# Power_supply.net
KiCad netlist of a schematic drawn in Altium Designer
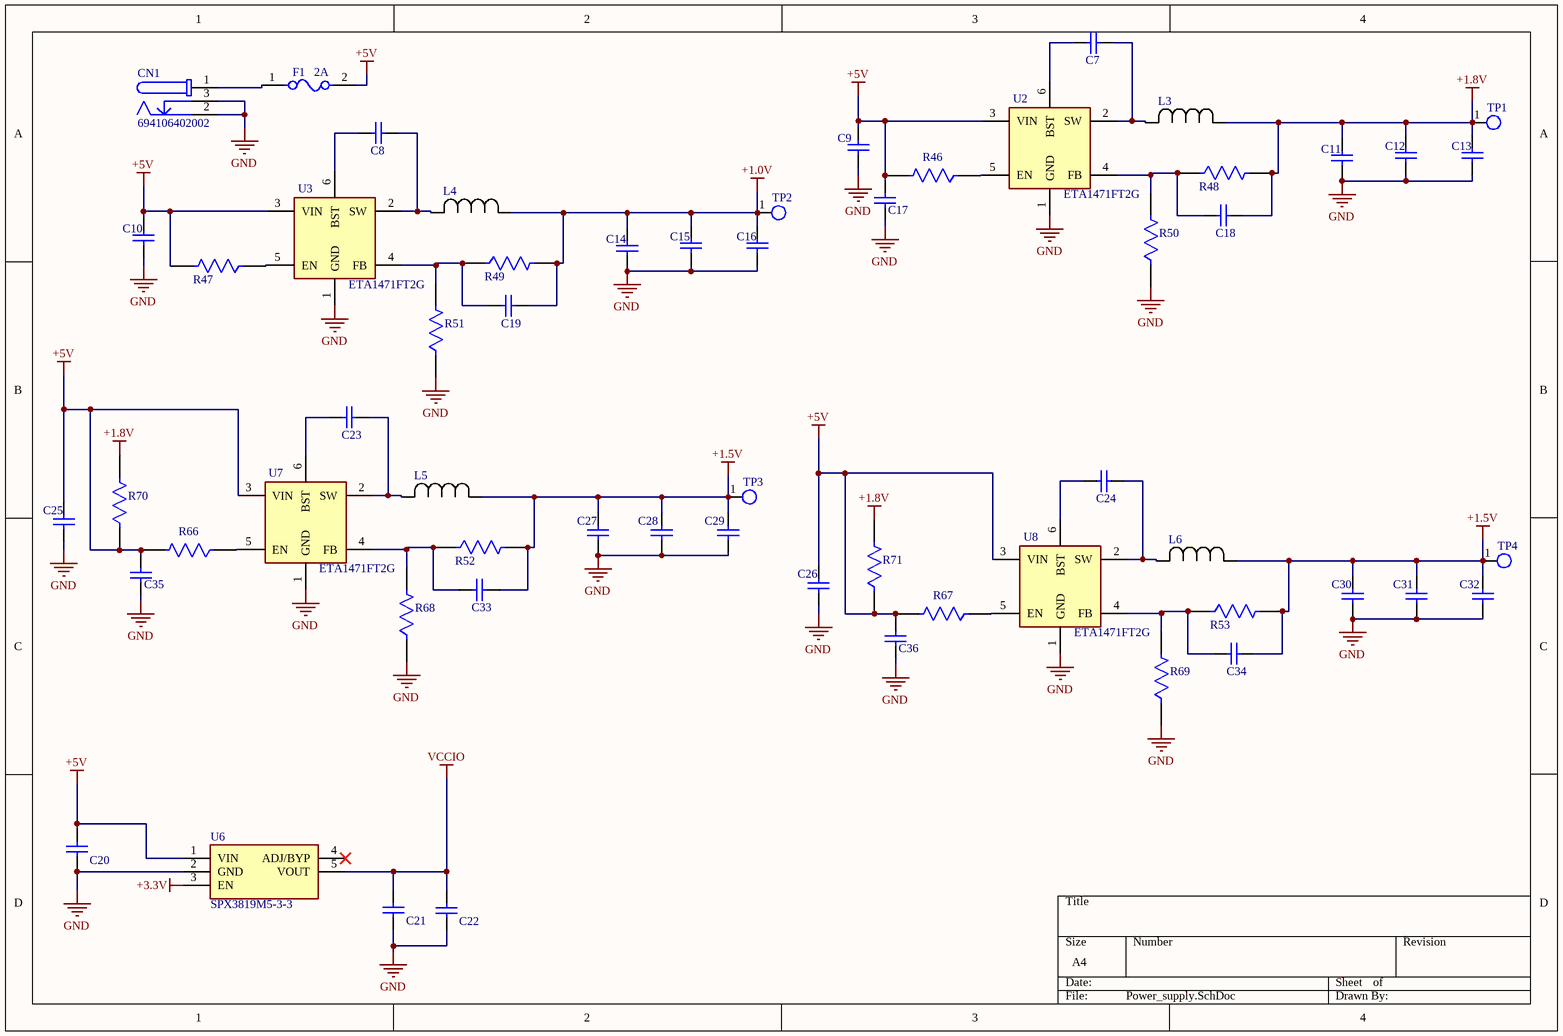
[diagram p0: Power_supply.SchDoc]

(export (version "E")
  (design (tool "Eeschema 10.0.6"))
  (components
    (comp (ref "C7")
      (value "VJ0805Y152KXAAC")
      (footprint "CAPC2013X145X48NL20T23")
      (fields (field (name "MANUFACTURER") "Vitramon"))
      (libsource (lib "Altium Content Vault") (part "CAP"))
    )
    (comp (ref "C8")
      (value "VJ0805Y152KXAAC")
      (footprint "CAPC2013X145X48NL20T23")
      (fields (field (name "MANUFACTURER") "Vitramon"))
      (libsource (lib "Altium Content Vault") (part "CAP"))
    )
    (comp (ref "C9")
      (value "VJ0805Y152KXAAC")
      (footprint "CAPC2013X145X48NL20T23")
      (fields (field (name "MANUFACTURER") "Vitramon"))
      (libsource (lib "Altium Content Vault") (part "CAP"))
    )
    (comp (ref "C10")
      (value "VJ0805Y152KXAAC")
      (footprint "CAPC2013X145X48NL20T23")
      (fields (field (name "MANUFACTURER") "Vitramon"))
      (libsource (lib "Altium Content Vault") (part "CAP"))
    )
    (comp (ref "C11")
      (value "VJ0805Y152KXAAC")
      (footprint "CAPC2013X145X48NL20T23")
      (fields (field (name "MANUFACTURER") "Vitramon"))
      (libsource (lib "Altium Content Vault") (part "CAP"))
    )
    (comp (ref "C12")
      (value "VJ0805Y152KXAAC")
      (footprint "CAPC2013X145X48NL20T23")
      (fields (field (name "MANUFACTURER") "Vitramon"))
      (libsource (lib "Altium Content Vault") (part "CAP"))
    )
    (comp (ref "C13")
      (value "VJ0805Y152KXAAC")
      (footprint "CAPC2013X145X48NL20T23")
      (fields (field (name "MANUFACTURER") "Vitramon"))
      (libsource (lib "Altium Content Vault") (part "CAP"))
    )
    (comp (ref "C14")
      (value "VJ0805Y152KXAAC")
      (footprint "CAPC2013X145X48NL20T23")
      (fields (field (name "MANUFACTURER") "Vitramon"))
      (libsource (lib "Altium Content Vault") (part "CAP"))
    )
    (comp (ref "C15")
      (value "VJ0805Y152KXAAC")
      (footprint "CAPC2013X145X48NL20T23")
      (fields (field (name "MANUFACTURER") "Vitramon"))
      (libsource (lib "Altium Content Vault") (part "CAP"))
    )
    (comp (ref "C16")
      (value "VJ0805Y152KXAAC")
      (footprint "CAPC2013X145X48NL20T23")
      (fields (field (name "MANUFACTURER") "Vitramon"))
      (libsource (lib "Altium Content Vault") (part "CAP"))
    )
    (comp (ref "C17")
      (value "VJ0805Y152KXAAC")
      (footprint "CAPC2013X145X48NL20T23")
      (fields (field (name "MANUFACTURER") "Vitramon"))
      (libsource (lib "Altium Content Vault") (part "CAP"))
    )
    (comp (ref "C18")
      (value "VJ0805Y152KXAAC")
      (footprint "CAPC2013X145X48NL20T23")
      (fields (field (name "MANUFACTURER") "Vitramon"))
      (libsource (lib "Altium Content Vault") (part "CAP"))
    )
    (comp (ref "C19")
      (value "VJ0805Y152KXAAC")
      (footprint "CAPC2013X145X48NL20T23")
      (fields (field (name "MANUFACTURER") "Vitramon"))
      (libsource (lib "Altium Content Vault") (part "CAP"))
    )
    (comp (ref "C20")
      (value "VJ0805Y152KXAAC")
      (footprint "CAPC2013X145X48NL20T23")
      (fields (field (name "MANUFACTURER") "Vitramon"))
      (libsource (lib "Altium Content Vault") (part "CAP"))
    )
    (comp (ref "C21")
      (value "VJ0805Y152KXAAC")
      (footprint "CAPC2013X145X48NL20T23")
      (fields (field (name "MANUFACTURER") "Vitramon"))
      (libsource (lib "Altium Content Vault") (part "CAP"))
    )
    (comp (ref "C22")
      (value "VJ0805Y152KXAAC")
      (footprint "CAPC2013X145X48NL20T23")
      (fields (field (name "MANUFACTURER") "Vitramon"))
      (libsource (lib "Altium Content Vault") (part "CAP"))
    )
    (comp (ref "C23")
      (value "VJ0805Y152KXAAC")
      (footprint "CAPC2013X145X48NL20T23")
      (fields (field (name "MANUFACTURER") "Vitramon"))
      (libsource (lib "Altium Content Vault") (part "CAP"))
    )
    (comp (ref "C24")
      (value "VJ0805Y152KXAAC")
      (footprint "CAPC2013X145X48NL20T23")
      (fields (field (name "MANUFACTURER") "Vitramon"))
      (libsource (lib "Altium Content Vault") (part "CAP"))
    )
    (comp (ref "C25")
      (value "VJ0805Y152KXAAC")
      (footprint "CAPC2013X145X48NL20T23")
      (fields (field (name "MANUFACTURER") "Vitramon"))
      (libsource (lib "Altium Content Vault") (part "CAP"))
    )
    (comp (ref "C26")
      (value "VJ0805Y152KXAAC")
      (footprint "CAPC2013X145X48NL20T23")
      (fields (field (name "MANUFACTURER") "Vitramon"))
      (libsource (lib "Altium Content Vault") (part "CAP"))
    )
    (comp (ref "C27")
      (value "VJ0805Y152KXAAC")
      (footprint "CAPC2013X145X48NL20T23")
      (fields (field (name "MANUFACTURER") "Vitramon"))
      (libsource (lib "Altium Content Vault") (part "CAP"))
    )
    (comp (ref "C28")
      (value "VJ0805Y152KXAAC")
      (footprint "CAPC2013X145X48NL20T23")
      (fields (field (name "MANUFACTURER") "Vitramon"))
      (libsource (lib "Altium Content Vault") (part "CAP"))
    )
    (comp (ref "C29")
      (value "VJ0805Y152KXAAC")
      (footprint "CAPC2013X145X48NL20T23")
      (fields (field (name "MANUFACTURER") "Vitramon"))
      (libsource (lib "Altium Content Vault") (part "CAP"))
    )
    (comp (ref "C30")
      (value "VJ0805Y152KXAAC")
      (footprint "CAPC2013X145X48NL20T23")
      (fields (field (name "MANUFACTURER") "Vitramon"))
      (libsource (lib "Altium Content Vault") (part "CAP"))
    )
    (comp (ref "C31")
      (value "VJ0805Y152KXAAC")
      (footprint "CAPC2013X145X48NL20T23")
      (fields (field (name "MANUFACTURER") "Vitramon"))
      (libsource (lib "Altium Content Vault") (part "CAP"))
    )
    (comp (ref "C32")
      (value "VJ0805Y152KXAAC")
      (footprint "CAPC2013X145X48NL20T23")
      (fields (field (name "MANUFACTURER") "Vitramon"))
      (libsource (lib "Altium Content Vault") (part "CAP"))
    )
    (comp (ref "C33")
      (value "VJ0805Y152KXAAC")
      (footprint "CAPC2013X145X48NL20T23")
      (fields (field (name "MANUFACTURER") "Vitramon"))
      (libsource (lib "Altium Content Vault") (part "CAP"))
    )
    (comp (ref "C34")
      (value "VJ0805Y152KXAAC")
      (footprint "CAPC2013X145X48NL20T23")
      (fields (field (name "MANUFACTURER") "Vitramon"))
      (libsource (lib "Altium Content Vault") (part "CAP"))
    )
    (comp (ref "C35")
      (value "VJ0805Y152KXAAC")
      (footprint "CAPC2013X145X48NL20T23")
      (fields (field (name "MANUFACTURER") "Vitramon"))
      (libsource (lib "Altium Content Vault") (part "CAP"))
    )
    (comp (ref "C36")
      (value "VJ0805Y152KXAAC")
      (footprint "CAPC2013X145X48NL20T23")
      (fields (field (name "MANUFACTURER") "Vitramon"))
      (libsource (lib "Altium Content Vault") (part "CAP"))
    )
    (comp (ref "CN1")
      (value "694106402002")
      (footprint "694106402002")
      (description "DC Power Jack Connector WR-DC, Male, Vertical, THT, 3 A, 20 V")
      (libsource (lib "Altium Content Vault") (part "DC Power Jack"))
    )
    (comp (ref "F1")
      (value "2A")
      (footprint "FP-0683G-MFG")
      (description "FUSE SLOW 125VDC 350VAC 2A")
      (libsource (lib "Altium Content Vault") (part "5bcf9b9f640e542cf0359d10258e979"))
    )
    (comp (ref "L3")
      (value "ASPIAIG-FLR4020-3R3M-T")
      (footprint "IND_ASPIAIG-F4020_ABR")
      (description "Description")
      (fields (field (name "COPYRIGHT") "Copyright (C) 2026 Ultra Librarian. All rights reserved."))
      (libsource (lib "ASPIAIG-FLR4020-3R3M-T") (part "ASPIAIG-FLR4020-3R3M-T"))
    )
    (comp (ref "L4")
      (value "ASPIAIG-FLR4020-3R3M-T")
      (footprint "IND_ASPIAIG-F4020_ABR")
      (description "Description")
      (fields (field (name "COPYRIGHT") "Copyright (C) 2026 Ultra Librarian. All rights reserved."))
      (libsource (lib "ASPIAIG-FLR4020-3R3M-T") (part "ASPIAIG-FLR4020-3R3M-T"))
    )
    (comp (ref "L5")
      (value "ASPIAIG-FLR4020-3R3M-T")
      (footprint "IND_ASPIAIG-F4020_ABR")
      (description "Description")
      (fields (field (name "COPYRIGHT") "Copyright (C) 2026 Ultra Librarian. All rights reserved."))
      (libsource (lib "ASPIAIG-FLR4020-3R3M-T") (part "ASPIAIG-FLR4020-3R3M-T"))
    )
    (comp (ref "L6")
      (value "ASPIAIG-FLR4020-3R3M-T")
      (footprint "IND_ASPIAIG-F4020_ABR")
      (description "Description")
      (fields (field (name "COPYRIGHT") "Copyright (C) 2026 Ultra Librarian. All rights reserved."))
      (libsource (lib "ASPIAIG-FLR4020-3R3M-T") (part "ASPIAIG-FLR4020-3R3M-T"))
    )
    (comp (ref "R46")
      (value "MCU0805MD4991BP100")
      (footprint "FP-MCU0805-MFG")
      (description "RES 1.05K OHM 0.5% 1/5W 0805")
      (fields (field (name "TOLERANCE") "0.1%"))
      (libsource (lib "Altium Content Vault") (part "1029c3af85768c4190bb7ad29bc67b5"))
    )
    (comp (ref "R47")
      (value "MCU0805MD4991BP100")
      (footprint "FP-MCU0805-MFG")
      (description "RES 1.05K OHM 0.5% 1/5W 0805")
      (fields (field (name "TOLERANCE") "0.1%"))
      (libsource (lib "Altium Content Vault") (part "1029c3af85768c4190bb7ad29bc67b5"))
    )
    (comp (ref "R48")
      (value "MCU0805MD4991BP100")
      (footprint "FP-MCU0805-MFG")
      (description "RES 1.05K OHM 0.5% 1/5W 0805")
      (fields (field (name "TOLERANCE") "0.1%"))
      (libsource (lib "Altium Content Vault") (part "1029c3af85768c4190bb7ad29bc67b5"))
    )
    (comp (ref "R49")
      (value "MCU0805MD4991BP100")
      (footprint "FP-MCU0805-MFG")
      (description "RES 1.05K OHM 0.5% 1/5W 0805")
      (fields (field (name "TOLERANCE") "0.1%"))
      (libsource (lib "Altium Content Vault") (part "1029c3af85768c4190bb7ad29bc67b5"))
    )
    (comp (ref "R50")
      (value "MCU0805MD4991BP100")
      (footprint "FP-MCU0805-MFG")
      (description "RES 1.05K OHM 0.5% 1/5W 0805")
      (fields (field (name "TOLERANCE") "0.1%"))
      (libsource (lib "Altium Content Vault") (part "1029c3af85768c4190bb7ad29bc67b5"))
    )
    (comp (ref "R51")
      (value "MCU0805MD4991BP100")
      (footprint "FP-MCU0805-MFG")
      (description "RES 1.05K OHM 0.5% 1/5W 0805")
      (fields (field (name "TOLERANCE") "0.1%"))
      (libsource (lib "Altium Content Vault") (part "1029c3af85768c4190bb7ad29bc67b5"))
    )
    (comp (ref "R52")
      (value "MCU0805MD4991BP100")
      (footprint "FP-MCU0805-MFG")
      (description "RES 1.05K OHM 0.5% 1/5W 0805")
      (fields (field (name "TOLERANCE") "0.1%"))
      (libsource (lib "Altium Content Vault") (part "1029c3af85768c4190bb7ad29bc67b5"))
    )
    (comp (ref "R53")
      (value "MCU0805MD4991BP100")
      (footprint "FP-MCU0805-MFG")
      (description "RES 1.05K OHM 0.5% 1/5W 0805")
      (fields (field (name "TOLERANCE") "0.1%"))
      (libsource (lib "Altium Content Vault") (part "1029c3af85768c4190bb7ad29bc67b5"))
    )
    (comp (ref "R66")
      (value "MCU0805MD4991BP100")
      (footprint "FP-MCU0805-MFG")
      (description "RES 1.05K OHM 0.5% 1/5W 0805")
      (fields (field (name "TOLERANCE") "0.1%"))
      (libsource (lib "Altium Content Vault") (part "1029c3af85768c4190bb7ad29bc67b5"))
    )
    (comp (ref "R67")
      (value "MCU0805MD4991BP100")
      (footprint "FP-MCU0805-MFG")
      (description "RES 1.05K OHM 0.5% 1/5W 0805")
      (fields (field (name "TOLERANCE") "0.1%"))
      (libsource (lib "Altium Content Vault") (part "1029c3af85768c4190bb7ad29bc67b5"))
    )
    (comp (ref "R68")
      (value "MCU0805MD4991BP100")
      (footprint "FP-MCU0805-MFG")
      (description "RES 1.05K OHM 0.5% 1/5W 0805")
      (fields (field (name "TOLERANCE") "0.1%"))
      (libsource (lib "Altium Content Vault") (part "1029c3af85768c4190bb7ad29bc67b5"))
    )
    (comp (ref "R69")
      (value "MCU0805MD4991BP100")
      (footprint "FP-MCU0805-MFG")
      (description "RES 1.05K OHM 0.5% 1/5W 0805")
      (fields (field (name "TOLERANCE") "0.1%"))
      (libsource (lib "Altium Content Vault") (part "1029c3af85768c4190bb7ad29bc67b5"))
    )
    (comp (ref "R70")
      (value "MCU0805MD4991BP100")
      (footprint "FP-MCU0805-MFG")
      (description "RES 1.05K OHM 0.5% 1/5W 0805")
      (fields (field (name "TOLERANCE") "0.1%"))
      (libsource (lib "Altium Content Vault") (part "1029c3af85768c4190bb7ad29bc67b5"))
    )
    (comp (ref "R71")
      (value "MCU0805MD4991BP100")
      (footprint "FP-MCU0805-MFG")
      (description "RES 1.05K OHM 0.5% 1/5W 0805")
      (fields (field (name "TOLERANCE") "0.1%"))
      (libsource (lib "Altium Content Vault") (part "1029c3af85768c4190bb7ad29bc67b5"))
    )
    (comp (ref "TP1") (value "testpoint") (libsource (lib "licenta") (part "testpoint")))
    (comp (ref "TP2") (value "testpoint") (libsource (lib "licenta") (part "testpoint")))
    (comp (ref "TP3") (value "testpoint") (libsource (lib "licenta") (part "testpoint")))
    (comp (ref "TP4") (value "testpoint") (libsource (lib "licenta") (part "testpoint")))
    (comp (ref "U2")
      (value "ETA1471FT2G")
      (footprint "SamacSys:SOT95P280X110-6N")
      (description "Integrated Circuit")
      (libsource (lib "SamacSys") (part "ETA1471FT2G"))
    )
    (comp (ref "U3")
      (value "ETA1471FT2G")
      (footprint "SamacSys:SOT95P280X110-6N")
      (description "Integrated Circuit")
      (libsource (lib "SamacSys") (part "ETA1471FT2G"))
    )
    (comp (ref "U6")
      (value "SPX3819M5-3-3")
      (footprint "SamacSys:SOT95P280X145-5N")
      (description "Integrated Circuit")
      (libsource (lib "*") (part "SPX3819M5-3-3"))
    )
    (comp (ref "U7")
      (value "ETA1471FT2G")
      (footprint "SamacSys:SOT95P280X110-6N")
      (description "Integrated Circuit")
      (libsource (lib "SamacSys") (part "ETA1471FT2G"))
    )
    (comp (ref "U8")
      (value "ETA1471FT2G")
      (footprint "SamacSys:SOT95P280X110-6N")
      (description "Integrated Circuit")
      (libsource (lib "SamacSys") (part "ETA1471FT2G"))
    )
  )
  (nets
    (net (code "1") (name "+1.0V") (class "Default")
      (node (ref "C14") (pin "2") (pinfunction "2_2") (pintype "passive"))
      (node (ref "C15") (pin "2") (pinfunction "2_2") (pintype "passive"))
      (node (ref "C16") (pin "2") (pinfunction "2_2") (pintype "passive"))
      (node (ref "C19") (pin "1") (pinfunction "1_1") (pintype "passive"))
      (node (ref "L4") (pin "1") (pinfunction "1_1") (pintype "passive"))
      (node (ref "R49") (pin "2") (pinfunction "2_2") (pintype "passive"))
      (node (ref "TP2") (pin "1") (pinfunction "1_1") (pintype "passive"))
    )
    (net (code "2") (name "+1.5V") (class "Default")
      (node (ref "C27") (pin "2") (pinfunction "2_2") (pintype "passive"))
      (node (ref "C28") (pin "2") (pinfunction "2_2") (pintype "passive"))
      (node (ref "C29") (pin "2") (pinfunction "2_2") (pintype "passive"))
      (node (ref "C30") (pin "2") (pinfunction "2_2") (pintype "passive"))
      (node (ref "C31") (pin "2") (pinfunction "2_2") (pintype "passive"))
      (node (ref "C32") (pin "2") (pinfunction "2_2") (pintype "passive"))
      (node (ref "C33") (pin "1") (pinfunction "1_1") (pintype "passive"))
      (node (ref "C34") (pin "1") (pinfunction "1_1") (pintype "passive"))
      (node (ref "L5") (pin "1") (pinfunction "1_1") (pintype "passive"))
      (node (ref "L6") (pin "1") (pinfunction "1_1") (pintype "passive"))
      (node (ref "R52") (pin "2") (pinfunction "2_2") (pintype "passive"))
      (node (ref "R53") (pin "2") (pinfunction "2_2") (pintype "passive"))
      (node (ref "TP3") (pin "1") (pinfunction "1_1") (pintype "passive"))
      (node (ref "TP4") (pin "1") (pinfunction "1_1") (pintype "passive"))
    )
    (net (code "3") (name "+1.8V") (class "Default")
      (node (ref "C11") (pin "2") (pinfunction "2_2") (pintype "passive"))
      (node (ref "C12") (pin "2") (pinfunction "2_2") (pintype "passive"))
      (node (ref "C13") (pin "2") (pinfunction "2_2") (pintype "passive"))
      (node (ref "C18") (pin "1") (pinfunction "1_1") (pintype "passive"))
      (node (ref "L3") (pin "1") (pinfunction "1_1") (pintype "passive"))
      (node (ref "R48") (pin "2") (pinfunction "2_2") (pintype "passive"))
      (node (ref "R70") (pin "2") (pinfunction "2_2") (pintype "passive"))
      (node (ref "R71") (pin "2") (pinfunction "2_2") (pintype "passive"))
      (node (ref "TP1") (pin "1") (pinfunction "1_1") (pintype "passive"))
    )
    (net (code "4") (name "+3.3V") (class "Default")
      (node (ref "U6") (pin "3") (pinfunction "EN_3") (pintype "passive"))
    )
    (net (code "5") (name "+5V") (class "Default")
      (node (ref "C10") (pin "1") (pinfunction "1_1") (pintype "passive"))
      (node (ref "C17") (pin "1") (pinfunction "1_1") (pintype "passive"))
      (node (ref "C20") (pin "1") (pinfunction "1_1") (pintype "passive"))
      (node (ref "C25") (pin "1") (pinfunction "1_1") (pintype "passive"))
      (node (ref "C26") (pin "1") (pinfunction "1_1") (pintype "passive"))
      (node (ref "C35") (pin "1") (pinfunction "1_1") (pintype "passive"))
      (node (ref "C36") (pin "1") (pinfunction "1_1") (pintype "passive"))
      (node (ref "C9") (pin "1") (pinfunction "1_1") (pintype "passive"))
      (node (ref "F1") (pin "2") (pinfunction "2_2") (pintype "passive"))
      (node (ref "R46") (pin "2") (pinfunction "2_2") (pintype "passive"))
      (node (ref "R47") (pin "2") (pinfunction "2_2") (pintype "passive"))
      (node (ref "R66") (pin "2") (pinfunction "2_2") (pintype "passive"))
      (node (ref "R67") (pin "2") (pinfunction "2_2") (pintype "passive"))
      (node (ref "R70") (pin "1") (pinfunction "1_1") (pintype "passive"))
      (node (ref "R71") (pin "1") (pinfunction "1_1") (pintype "passive"))
      (node (ref "U2") (pin "3") (pinfunction "VIN_3") (pintype "passive"))
      (node (ref "U3") (pin "3") (pinfunction "VIN_3") (pintype "passive"))
      (node (ref "U6") (pin "1") (pinfunction "VIN_1") (pintype "passive"))
      (node (ref "U7") (pin "3") (pinfunction "VIN_3") (pintype "passive"))
      (node (ref "U8") (pin "3") (pinfunction "VIN_3") (pintype "passive"))
    )
    (net (code "6") (name "GND") (class "Default")
      (node (ref "C10") (pin "2") (pinfunction "2_2") (pintype "passive"))
      (node (ref "C11") (pin "1") (pinfunction "1_1") (pintype "passive"))
      (node (ref "C12") (pin "1") (pinfunction "1_1") (pintype "passive"))
      (node (ref "C13") (pin "1") (pinfunction "1_1") (pintype "passive"))
      (node (ref "C14") (pin "1") (pinfunction "1_1") (pintype "passive"))
      (node (ref "C15") (pin "1") (pinfunction "1_1") (pintype "passive"))
      (node (ref "C16") (pin "1") (pinfunction "1_1") (pintype "passive"))
      (node (ref "C17") (pin "2") (pinfunction "2_2") (pintype "passive"))
      (node (ref "C20") (pin "2") (pinfunction "2_2") (pintype "passive"))
      (node (ref "C21") (pin "2") (pinfunction "2_2") (pintype "passive"))
      (node (ref "C22") (pin "2") (pinfunction "2_2") (pintype "passive"))
      (node (ref "C25") (pin "2") (pinfunction "2_2") (pintype "passive"))
      (node (ref "C26") (pin "2") (pinfunction "2_2") (pintype "passive"))
      (node (ref "C27") (pin "1") (pinfunction "1_1") (pintype "passive"))
      (node (ref "C28") (pin "1") (pinfunction "1_1") (pintype "passive"))
      (node (ref "C29") (pin "1") (pinfunction "1_1") (pintype "passive"))
      (node (ref "C30") (pin "1") (pinfunction "1_1") (pintype "passive"))
      (node (ref "C31") (pin "1") (pinfunction "1_1") (pintype "passive"))
      (node (ref "C32") (pin "1") (pinfunction "1_1") (pintype "passive"))
      (node (ref "C35") (pin "2") (pinfunction "2_2") (pintype "passive"))
      (node (ref "C36") (pin "2") (pinfunction "2_2") (pintype "passive"))
      (node (ref "C9") (pin "2") (pinfunction "2_2") (pintype "passive"))
      (node (ref "CN1") (pin "2") (pinfunction "2_2") (pintype "passive"))
      (node (ref "CN1") (pin "3") (pinfunction "3_3") (pintype "passive"))
      (node (ref "R50") (pin "1") (pinfunction "1_1") (pintype "passive"))
      (node (ref "R51") (pin "1") (pinfunction "1_1") (pintype "passive"))
      (node (ref "R68") (pin "1") (pinfunction "1_1") (pintype "passive"))
      (node (ref "R69") (pin "1") (pinfunction "1_1") (pintype "passive"))
      (node (ref "U2") (pin "1") (pinfunction "GND_1") (pintype "passive"))
      (node (ref "U3") (pin "1") (pinfunction "GND_1") (pintype "passive"))
      (node (ref "U6") (pin "2") (pinfunction "GND_2") (pintype "passive"))
      (node (ref "U7") (pin "1") (pinfunction "GND_1") (pintype "passive"))
      (node (ref "U8") (pin "1") (pinfunction "GND_1") (pintype "passive"))
    )
    (net (code "7") (name "Net-(CN1-Pad1)") (class "Default")
      (node (ref "CN1") (pin "1") (pinfunction "1_1") (pintype "passive"))
      (node (ref "F1") (pin "1") (pinfunction "1_1") (pintype "passive"))
    )
    (net (code "8") (name "Net-(U2-BST)") (class "Default")
      (node (ref "C7") (pin "2") (pinfunction "2_2") (pintype "passive"))
      (node (ref "U2") (pin "6") (pinfunction "BST_6") (pintype "passive"))
    )
    (net (code "9") (name "Net-(U2-EN)") (class "Default")
      (node (ref "R46") (pin "1") (pinfunction "1_1") (pintype "passive"))
      (node (ref "U2") (pin "5") (pinfunction "EN_5") (pintype "passive"))
    )
    (net (code "10") (name "Net-(U2-FB)") (class "Default")
      (node (ref "C18") (pin "2") (pinfunction "2_2") (pintype "passive"))
      (node (ref "R48") (pin "1") (pinfunction "1_1") (pintype "passive"))
      (node (ref "R50") (pin "2") (pinfunction "2_2") (pintype "passive"))
      (node (ref "U2") (pin "4") (pinfunction "FB_4") (pintype "passive"))
    )
    (net (code "11") (name "Net-(U2-SW)") (class "Default")
      (node (ref "C7") (pin "1") (pinfunction "1_1") (pintype "passive"))
      (node (ref "L3") (pin "2") (pinfunction "2_2") (pintype "passive"))
      (node (ref "U2") (pin "2") (pinfunction "SW_2") (pintype "passive"))
    )
    (net (code "12") (name "Net-(U3-BST)") (class "Default")
      (node (ref "C8") (pin "2") (pinfunction "2_2") (pintype "passive"))
      (node (ref "U3") (pin "6") (pinfunction "BST_6") (pintype "passive"))
    )
    (net (code "13") (name "Net-(U3-EN)") (class "Default")
      (node (ref "R47") (pin "1") (pinfunction "1_1") (pintype "passive"))
      (node (ref "U3") (pin "5") (pinfunction "EN_5") (pintype "passive"))
    )
    (net (code "14") (name "Net-(U3-FB)") (class "Default")
      (node (ref "C19") (pin "2") (pinfunction "2_2") (pintype "passive"))
      (node (ref "R49") (pin "1") (pinfunction "1_1") (pintype "passive"))
      (node (ref "R51") (pin "2") (pinfunction "2_2") (pintype "passive"))
      (node (ref "U3") (pin "4") (pinfunction "FB_4") (pintype "passive"))
    )
    (net (code "15") (name "Net-(U3-SW)") (class "Default")
      (node (ref "C8") (pin "1") (pinfunction "1_1") (pintype "passive"))
      (node (ref "L4") (pin "2") (pinfunction "2_2") (pintype "passive"))
      (node (ref "U3") (pin "2") (pinfunction "SW_2") (pintype "passive"))
    )
    (net (code "16") (name "Net-(U7-BST)") (class "Default")
      (node (ref "C23") (pin "2") (pinfunction "2_2") (pintype "passive"))
      (node (ref "U7") (pin "6") (pinfunction "BST_6") (pintype "passive"))
    )
    (net (code "17") (name "Net-(U7-EN)") (class "Default")
      (node (ref "R66") (pin "1") (pinfunction "1_1") (pintype "passive"))
      (node (ref "U7") (pin "5") (pinfunction "EN_5") (pintype "passive"))
    )
    (net (code "18") (name "Net-(U7-FB)") (class "Default")
      (node (ref "C33") (pin "2") (pinfunction "2_2") (pintype "passive"))
      (node (ref "R52") (pin "1") (pinfunction "1_1") (pintype "passive"))
      (node (ref "R68") (pin "2") (pinfunction "2_2") (pintype "passive"))
      (node (ref "U7") (pin "4") (pinfunction "FB_4") (pintype "passive"))
    )
    (net (code "19") (name "Net-(U7-SW)") (class "Default")
      (node (ref "C23") (pin "1") (pinfunction "1_1") (pintype "passive"))
      (node (ref "L5") (pin "2") (pinfunction "2_2") (pintype "passive"))
      (node (ref "U7") (pin "2") (pinfunction "SW_2") (pintype "passive"))
    )
    (net (code "20") (name "Net-(U8-BST)") (class "Default")
      (node (ref "C24") (pin "2") (pinfunction "2_2") (pintype "passive"))
      (node (ref "U8") (pin "6") (pinfunction "BST_6") (pintype "passive"))
    )
    (net (code "21") (name "Net-(U8-EN)") (class "Default")
      (node (ref "R67") (pin "1") (pinfunction "1_1") (pintype "passive"))
      (node (ref "U8") (pin "5") (pinfunction "EN_5") (pintype "passive"))
    )
    (net (code "22") (name "Net-(U8-FB)") (class "Default")
      (node (ref "C34") (pin "2") (pinfunction "2_2") (pintype "passive"))
      (node (ref "R53") (pin "1") (pinfunction "1_1") (pintype "passive"))
      (node (ref "R69") (pin "2") (pinfunction "2_2") (pintype "passive"))
      (node (ref "U8") (pin "4") (pinfunction "FB_4") (pintype "passive"))
    )
    (net (code "23") (name "Net-(U8-SW)") (class "Default")
      (node (ref "C24") (pin "1") (pinfunction "1_1") (pintype "passive"))
      (node (ref "L6") (pin "2") (pinfunction "2_2") (pintype "passive"))
      (node (ref "U8") (pin "2") (pinfunction "SW_2") (pintype "passive"))
    )
    (net (code "24") (name "VCCIO") (class "Default")
      (node (ref "C21") (pin "1") (pinfunction "1_1") (pintype "passive"))
      (node (ref "C22") (pin "1") (pinfunction "1_1") (pintype "passive"))
      (node (ref "U6") (pin "5") (pinfunction "VOUT_5") (pintype "passive"))
    )
    (net (code "25") (name "unconnected-(U6-ADJ{slash}BYP-Pad4)") (class "Default")
      (node (ref "U6") (pin "4") (pinfunction "ADJ/BYP_4") (pintype "passive+no_connect"))
    )
  )
)
